# Discharge.net
KiCad netlist of a schematic drawn in Altium Designer
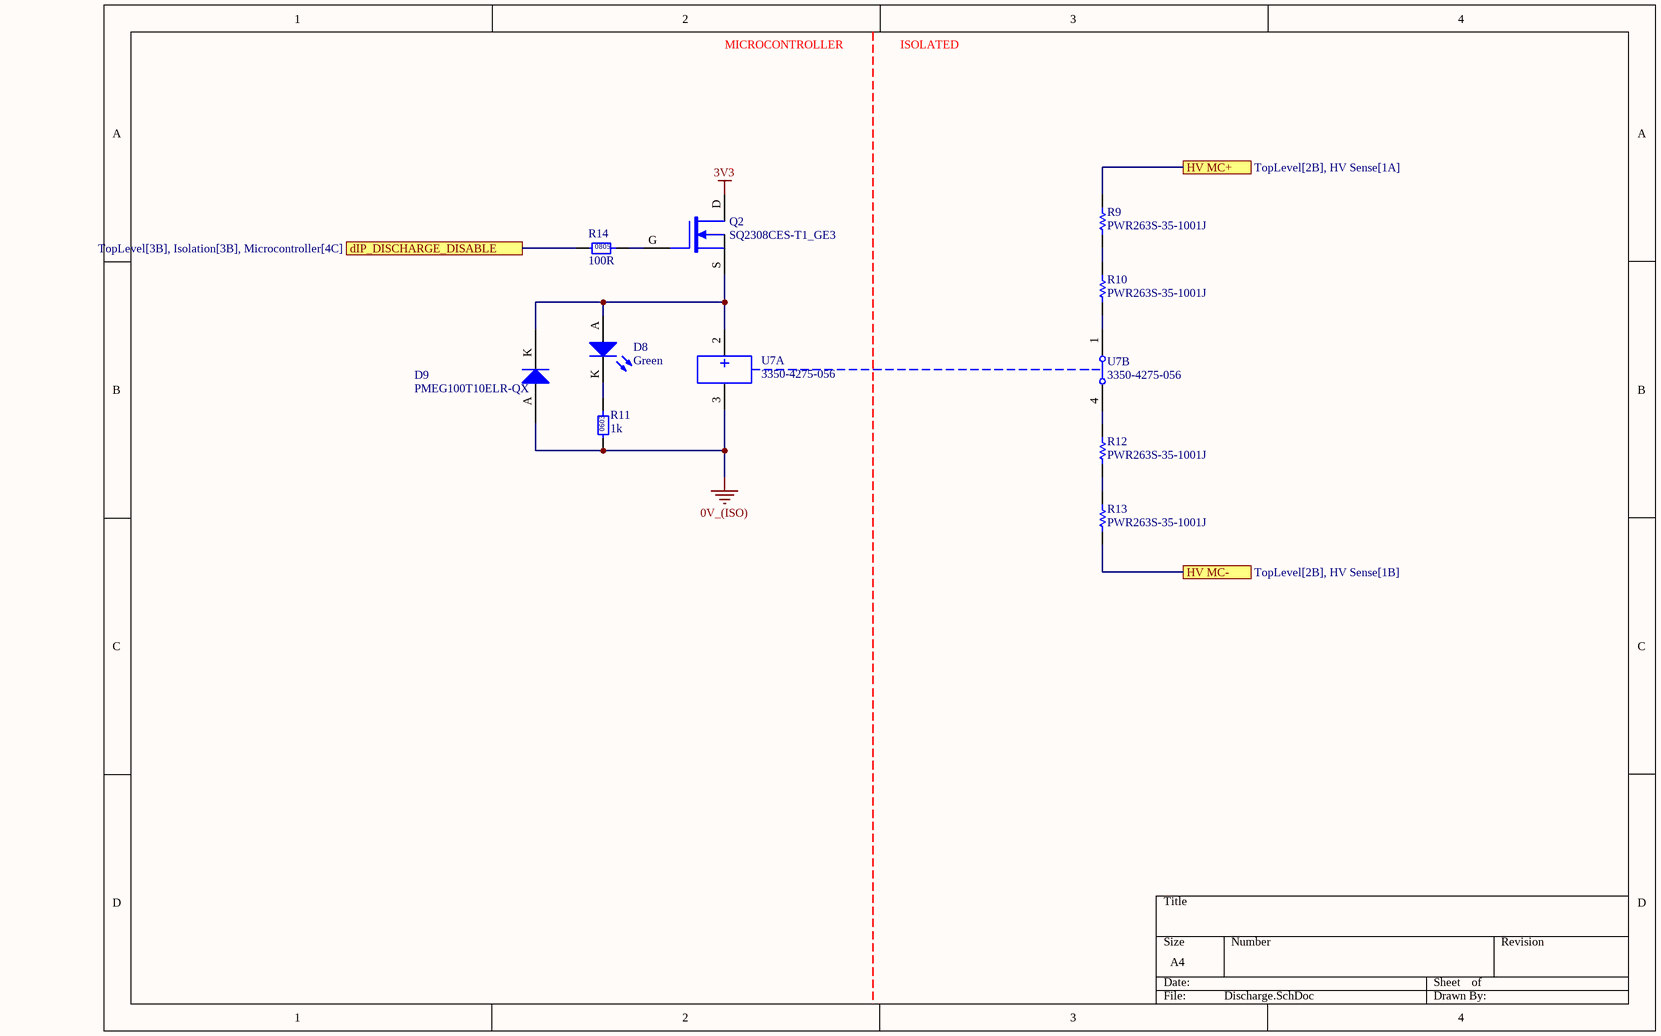
[diagram p0: Discharge.SchDoc]

(export (version "E")
  (design (tool "Eeschema 10.0.6"))
  (components
    (comp (ref "D8")
      (value "Green")
      (footprint "0805 LED")
      (description "Green LED Indication - Discrete 1.75V 0805 (2012 Metric)")
      (fields (field (name "PART NUMBER") "SML-210FTT86") (field (name "MANUFACTURER") "ROHM Semiconductor"))
      (libsource (lib "ts_standard_library") (part "LED"))
    )
    (comp (ref "D9")
      (value "PMEG100T10ELR-QX")
      (footprint "SODFL350X110-2N")
      (description "Diode 100 V 1A Surface Mount SOD-123W")
      (libsource (lib "Team Swinburne") (part "PMEG100T10ELR-QX"))
    )
    (comp (ref "Q2")
      (value "SQ2308CES-T1_GE3")
      (footprint "VSHY SOT-23-3")
      (description "MOSFET N-CH 60V 2.3A SOT23")
      (fields
        (field (name "MANUFACTURER") "Vishay Siliconix")
        (field (name "DIGIKEY PART NUMBER") "SQ2308CES-T1_GE3CT-ND")
        (field (name "PUBLISHER") "Altium Limited")
      )
      (libsource (lib "ts_standard_library") (part "MOSFET-N"))
    )
    (comp (ref "R9")
      (value "PWR263S-35-1001J")
      (footprint "B TO-263")
      (fields
        (field (name "MANUFACTURER") "Bournes Inc")
        (field (name "TOLERANCE") "0.05")
        (field (name "DIGIKEY PART NUMBER") "PWR263S-35-1001J-ND")
      )
      (libsource (lib "Team Swinburne") (part "Resistor"))
    )
    (comp (ref "R10")
      (value "PWR263S-35-1001J")
      (footprint "B TO-263")
      (fields
        (field (name "MANUFACTURER") "Bournes Inc")
        (field (name "TOLERANCE") "0.05")
        (field (name "DIGIKEY PART NUMBER") "PWR263S-35-1001J-ND")
      )
      (libsource (lib "Team Swinburne") (part "Resistor"))
    )
    (comp (ref "R11")
      (value "1k")
      (footprint "0603")
      (fields
        (field (name "PART NUMBER") "RC0603FR-071KL")
        (field (name "MANUFACTURER") "YAGEO")
        (field (name "TOLERANCE") "0.01")
      )
      (libsource (lib "ts_standard_library") (part "Resistor 0603"))
    )
    (comp (ref "R12")
      (value "PWR263S-35-1001J")
      (footprint "B TO-263")
      (fields
        (field (name "MANUFACTURER") "Bournes Inc")
        (field (name "TOLERANCE") "0.05")
        (field (name "DIGIKEY PART NUMBER") "PWR263S-35-1001J-ND")
      )
      (libsource (lib "Team Swinburne") (part "Resistor"))
    )
    (comp (ref "R13")
      (value "PWR263S-35-1001J")
      (footprint "B TO-263")
      (fields
        (field (name "MANUFACTURER") "Bournes Inc")
        (field (name "TOLERANCE") "0.05")
        (field (name "DIGIKEY PART NUMBER") "PWR263S-35-1001J-ND")
      )
      (libsource (lib "Team Swinburne") (part "Resistor"))
    )
    (comp (ref "R14")
      (value "100R")
      (footprint "0805")
      (fields
        (field (name "PART NUMBER") "RC0805FR07100RL")
        (field (name "MANUFACTURER") "YAGEO")
        (field (name "TOLERANCE") "0.01")
      )
      (libsource (lib "ts_standard_library") (part "Resistor 0805"))
    )
    (comp (ref "U7")
      (value "3350-4275-056")
      (footprint "CI SPST")
      (description "RELAY REED HV SPST 200W 3A 5V (NC)")
      (libsource (lib "Team Swinburne") (part "3350-4275-056"))
    )
  )
  (nets
    (net (code "1") (name "/HV MC+") (class "Default")
      (node (ref "R9") (pin "1") (pinfunction "1_1") (pintype "passive"))
    )
    (net (code "2") (name "/HV MC-") (class "Default")
      (node (ref "R13") (pin "2") (pinfunction "2_2") (pintype "passive"))
    )
    (net (code "3") (name "/dIP_DISCHARGE_DISABLE") (class "Default")
      (node (ref "R14") (pin "1") (pinfunction "1_1") (pintype "passive"))
    )
    (net (code "4") (name "0V_(ISO)") (class "Default")
      (node (ref "D9") (pin "A") (pintype "passive"))
      (node (ref "R11") (pin "1") (pinfunction "1_1") (pintype "passive"))
      (node (ref "U7") (pin "3") (pinfunction "3_3") (pintype "passive"))
    )
    (net (code "5") (name "3V3") (class "Default")
      (node (ref "Q2") (pin "D") (pinfunction "D_D") (pintype "passive"))
    )
    (net (code "6") (name "Net-(D8-PadA)") (class "Default")
      (node (ref "D8") (pin "A") (pinfunction "A_A") (pintype "passive"))
      (node (ref "D9") (pin "K") (pintype "passive"))
      (node (ref "Q2") (pin "S") (pinfunction "S_S") (pintype "passive"))
      (node (ref "U7") (pin "2") (pinfunction "2_2") (pintype "passive"))
    )
    (net (code "7") (name "Net-(D8-PadK)") (class "Default")
      (node (ref "D8") (pin "K") (pinfunction "K_K") (pintype "passive"))
      (node (ref "R11") (pin "2") (pinfunction "2_2") (pintype "passive"))
    )
    (net (code "8") (name "Net-(Q2-PadG)") (class "Default")
      (node (ref "Q2") (pin "G") (pinfunction "G_G") (pintype "passive"))
      (node (ref "R14") (pin "2") (pinfunction "2_2") (pintype "passive"))
    )
    (net (code "9") (name "Net-(R10-Pad1)") (class "Default")
      (node (ref "R10") (pin "1") (pinfunction "1_1") (pintype "passive"))
      (node (ref "R9") (pin "2") (pinfunction "2_2") (pintype "passive"))
    )
    (net (code "10") (name "Net-(R10-Pad2)") (class "Default")
      (node (ref "R10") (pin "2") (pinfunction "2_2") (pintype "passive"))
      (node (ref "U7") (pin "1") (pinfunction "1_1") (pintype "passive"))
    )
    (net (code "11") (name "Net-(R12-Pad1)") (class "Default")
      (node (ref "R12") (pin "1") (pinfunction "1_1") (pintype "passive"))
      (node (ref "U7") (pin "4") (pinfunction "4_4") (pintype "passive"))
    )
    (net (code "12") (name "Net-(R12-Pad2)") (class "Default")
      (node (ref "R12") (pin "2") (pinfunction "2_2") (pintype "passive"))
      (node (ref "R13") (pin "1") (pinfunction "1_1") (pintype "passive"))
    )
  )
)
